# adc-ADS7952.net
KiCad netlist of a schematic drawn in Altium Designer
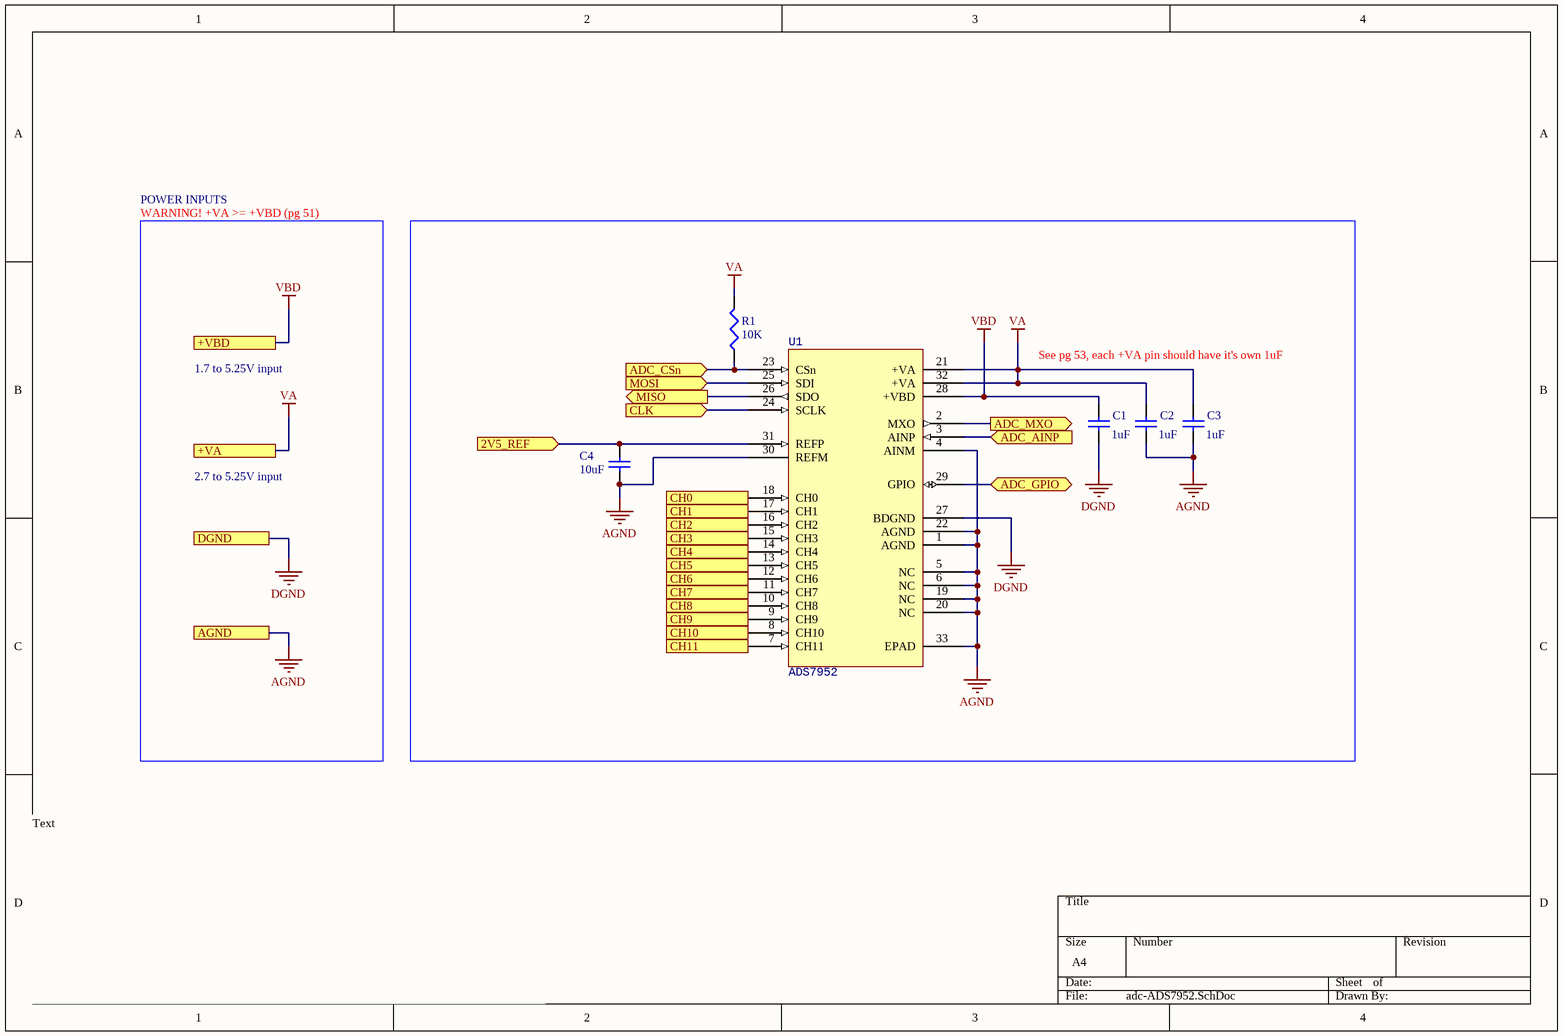
[diagram p0: adc-ADS7952.SchDoc]

(export (version "E")
  (design (tool "Eeschema 10.0.6"))
  (components
    (comp (ref "C1")
      (value "1uF")
      (footprint "1608[0603]")
      (description "Capacitor (Semiconductor SIM Model)")
      (fields (field (name "PUBLISHER") "Altium Limited"))
      (libsource (lib "Miscellaneous Devices") (part "Cap Semi"))
    )
    (comp (ref "C2")
      (value "1uF")
      (footprint "1608[0603]")
      (description "Capacitor (Semiconductor SIM Model)")
      (fields (field (name "PUBLISHER") "Altium Limited"))
      (libsource (lib "Miscellaneous Devices") (part "Cap Semi"))
    )
    (comp (ref "C3")
      (value "1uF")
      (footprint "1608[0603]")
      (description "Capacitor (Semiconductor SIM Model)")
      (fields (field (name "PUBLISHER") "Altium Limited"))
      (libsource (lib "Miscellaneous Devices") (part "Cap Semi"))
    )
    (comp (ref "C4")
      (value "10uF")
      (footprint "1608[0603]")
      (description "Capacitor")
      (fields (field (name "PUBLISHER") "Altium Limited"))
      (libsource (lib "Miscellaneous Devices") (part "Cap"))
    )
    (comp (ref "R1")
      (value "10K")
      (footprint "J1-0603")
      (description "Resistor")
      (fields (field (name "PUBLISHER") "Altium Limited"))
      (libsource (lib "Miscellaneous Devices") (part "Res3"))
    )
    (comp (ref "U1")
      (value "ADS7952")
      (footprint "QFN50P500X500X100-33")
      (description "12 bit, 12 channel analog-to-digital converter with SPI interface.")
      (libsource (lib "ICs") (part "ADS7952"))
    )
  )
  (nets
    (net (code "1") (name "/2V5_REF") (class "Default")
      (node (ref "C4") (pin "2") (pinfunction "2_2") (pintype "passive"))
      (node (ref "U1") (pin "31") (pinfunction "REFP_31") (pintype "input"))
    )
    (net (code "2") (name "/ADC_AINP") (class "Default")
      (node (ref "U1") (pin "3") (pinfunction "AINP_3") (pintype "input"))
    )
    (net (code "3") (name "/ADC_CSn") (class "Default")
      (node (ref "R1") (pin "1") (pinfunction "1_1") (pintype "passive"))
      (node (ref "U1") (pin "23") (pinfunction "CSn_23") (pintype "input"))
    )
    (net (code "4") (name "/ADC_GPIO") (class "Default")
      (node (ref "U1") (pin "29") (pinfunction "GPIO_29") (pintype "bidirectional"))
    )
    (net (code "5") (name "/ADC_MXO") (class "Default")
      (node (ref "U1") (pin "2") (pinfunction "MXO_2") (pintype "output"))
    )
    (net (code "6") (name "/CH0") (class "Default")
      (node (ref "U1") (pin "18") (pinfunction "CH0_18") (pintype "input"))
    )
    (net (code "7") (name "/CH1") (class "Default")
      (node (ref "U1") (pin "17") (pinfunction "CH1_17") (pintype "input"))
    )
    (net (code "8") (name "/CH2") (class "Default")
      (node (ref "U1") (pin "16") (pinfunction "CH2_16") (pintype "input"))
    )
    (net (code "9") (name "/CH3") (class "Default")
      (node (ref "U1") (pin "15") (pinfunction "CH3_15") (pintype "input"))
    )
    (net (code "10") (name "/CH4") (class "Default")
      (node (ref "U1") (pin "14") (pinfunction "CH4_14") (pintype "input"))
    )
    (net (code "11") (name "/CH5") (class "Default")
      (node (ref "U1") (pin "13") (pinfunction "CH5_13") (pintype "input"))
    )
    (net (code "12") (name "/CH6") (class "Default")
      (node (ref "U1") (pin "12") (pinfunction "CH6_12") (pintype "input"))
    )
    (net (code "13") (name "/CH7") (class "Default")
      (node (ref "U1") (pin "11") (pinfunction "CH7_11") (pintype "input"))
    )
    (net (code "14") (name "/CH8") (class "Default")
      (node (ref "U1") (pin "10") (pinfunction "CH8_10") (pintype "input"))
    )
    (net (code "15") (name "/CH9") (class "Default")
      (node (ref "U1") (pin "9") (pinfunction "CH9_9") (pintype "input"))
    )
    (net (code "16") (name "/CH10") (class "Default")
      (node (ref "U1") (pin "8") (pinfunction "CH10_8") (pintype "input"))
    )
    (net (code "17") (name "/CH11") (class "Default")
      (node (ref "U1") (pin "7") (pinfunction "CH11_7") (pintype "input"))
    )
    (net (code "18") (name "/CLK") (class "Default")
      (node (ref "U1") (pin "24") (pinfunction "SCLK_24") (pintype "input"))
    )
    (net (code "19") (name "/MISO") (class "Default")
      (node (ref "U1") (pin "26") (pinfunction "SDO_26") (pintype "output"))
    )
    (net (code "20") (name "/MOSI") (class "Default")
      (node (ref "U1") (pin "25") (pinfunction "SDI_25") (pintype "input"))
    )
    (net (code "21") (name "AGND") (class "Default")
      (node (ref "C2") (pin "1") (pinfunction "1_1") (pintype "passive"))
      (node (ref "C3") (pin "1") (pinfunction "1_1") (pintype "passive"))
      (node (ref "C4") (pin "1") (pinfunction "1_1") (pintype "passive"))
      (node (ref "U1") (pin "1") (pinfunction "AGND_1") (pintype "power_in"))
      (node (ref "U1") (pin "19") (pinfunction "NC_19") (pintype "passive"))
      (node (ref "U1") (pin "20") (pinfunction "NC_20") (pintype "passive"))
      (node (ref "U1") (pin "22") (pinfunction "AGND_22") (pintype "power_in"))
      (node (ref "U1") (pin "30") (pinfunction "REFM_30") (pintype "power_in"))
      (node (ref "U1") (pin "33") (pinfunction "EPAD_33") (pintype "power_in"))
      (node (ref "U1") (pin "4") (pinfunction "AINM_4") (pintype "power_in"))
      (node (ref "U1") (pin "5") (pinfunction "NC_5") (pintype "passive"))
      (node (ref "U1") (pin "6") (pinfunction "NC_6") (pintype "passive"))
    )
    (net (code "22") (name "DGND") (class "Default")
      (node (ref "C1") (pin "1") (pinfunction "1_1") (pintype "passive"))
      (node (ref "U1") (pin "27") (pinfunction "BDGND_27") (pintype "power_in"))
    )
    (net (code "23") (name "VA") (class "Default")
      (node (ref "C2") (pin "2") (pinfunction "2_2") (pintype "passive"))
      (node (ref "C3") (pin "2") (pinfunction "2_2") (pintype "passive"))
      (node (ref "R1") (pin "2") (pinfunction "2_2") (pintype "passive"))
      (node (ref "U1") (pin "21") (pinfunction "+VA_21") (pintype "power_in"))
      (node (ref "U1") (pin "32") (pinfunction "+VA_32") (pintype "power_in"))
    )
    (net (code "24") (name "VBD") (class "Default")
      (node (ref "C1") (pin "2") (pinfunction "2_2") (pintype "passive"))
      (node (ref "U1") (pin "28") (pinfunction "+VBD_28") (pintype "power_in"))
    )
  )
)
